# MCU.net
KiCad netlist of a schematic drawn in Altium Designer
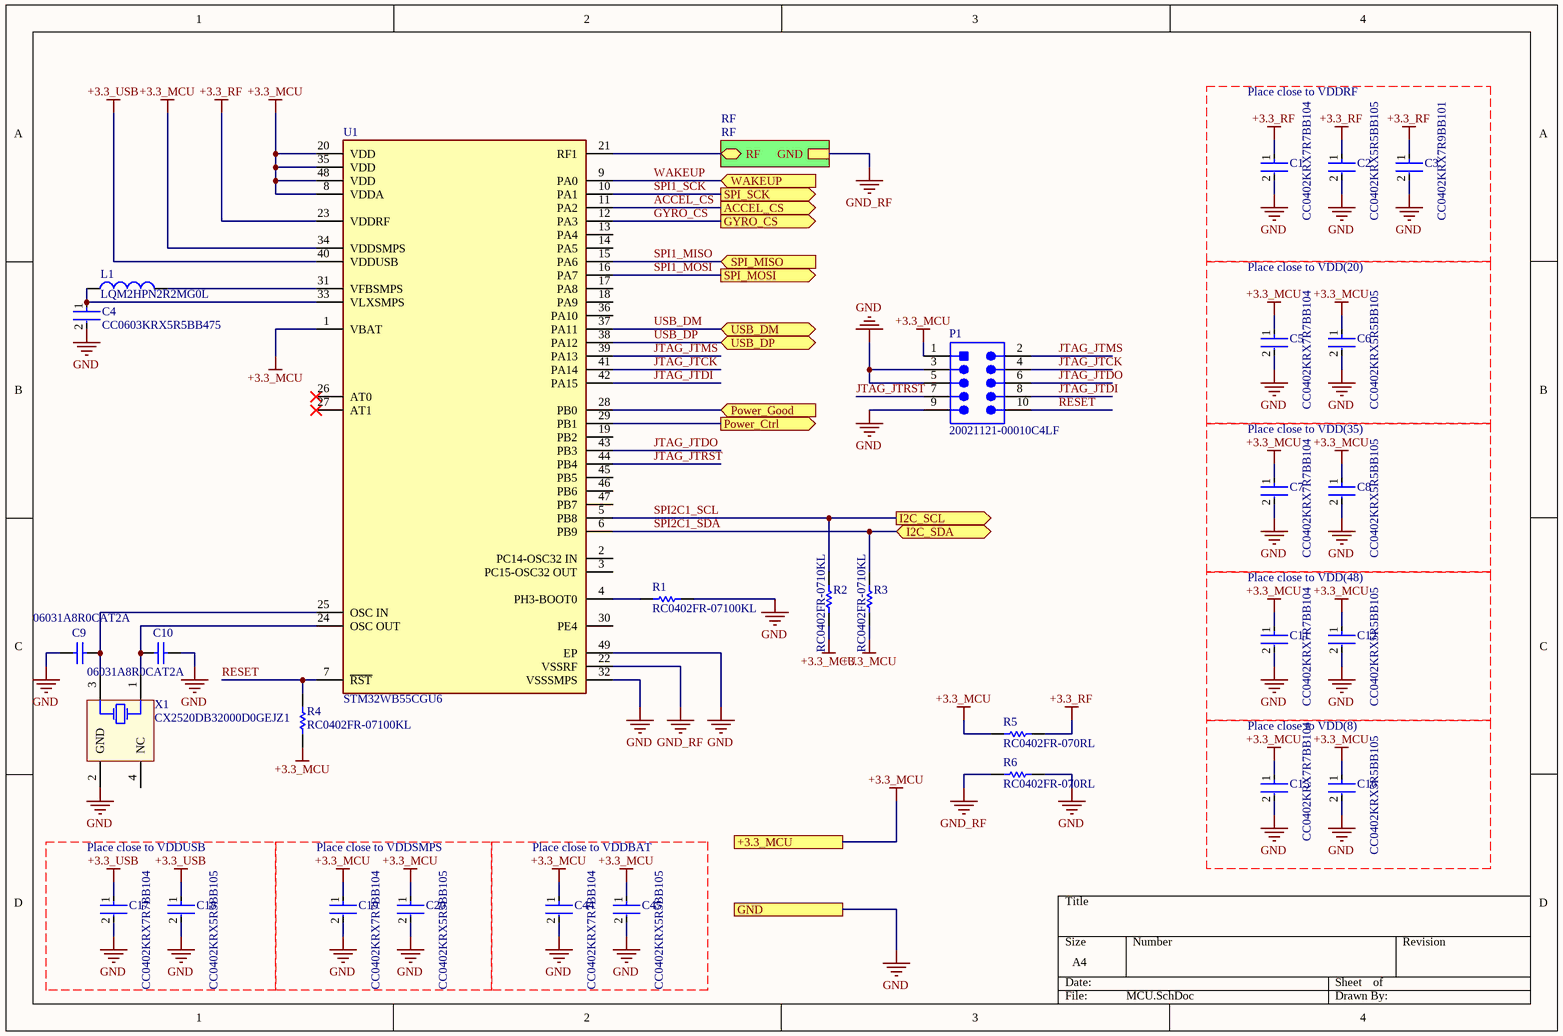
[diagram p0: MCU.SchDoc]

(export (version "E")
  (design (tool "Eeschema 10.0.6"))
  (components
    (comp (ref "C1")
      (value "CC0402KRX7R7BB104")
      (footprint "FP-CC0402-MFG")
      (description "CAP CER 0.1UF 16V X7R 0402")
      (fields (field (name "MANUFACTURER") "YAGEO") (field (name "TOLERANCE") "0.1"))
      (libsource (lib "Altium Content Vault") (part "11868f565c42a9108669ba33697ecf6"))
    )
    (comp (ref "C2")
      (value "CC0402KRX5R5BB105")
      (footprint "FP-CC0402-MFG")
      (description "CAP CER 1UF 6.3V X5R 0402")
      (fields
        (field (name "MANUFACTURER") "YAGEO")
        (field (name "OCTOPART") "https://octopart.com/cc0402krx5r5bb105-yageo-42244618")
      )
      (libsource (lib "Altium Content Vault") (part "11868f565c42a9108669ba33697ecf6"))
    )
    (comp (ref "C3")
      (value "CC0402KRX7R9BB101")
      (footprint "FP-CC0402-MFG")
      (description "CAP CER 100PF 50V X7R 0402")
      (fields
        (field (name "MANUFACTURER") "YAGEO")
        (field (name "OCTOPART") "https://octopart.com/cc0402krx7r9bb101-yageo-42334067")
      )
      (libsource (lib "Altium Content Vault") (part "11868f565c42a9108669ba33697ecf6"))
    )
    (comp (ref "C4")
      (value "CC0603KRX5R5BB475")
      (footprint "FP-CC0603-DA-MFG")
      (description "CAP CER 4.7UF 6.3V X5R 0603")
      (fields (field (name "TOLERANCE") "0.1") (field (name "VOLTAGE") "6.3 V"))
      (libsource (lib "Altium Content Vault") (part "11868f565c42a9108669ba33697ecf6"))
    )
    (comp (ref "C5")
      (value "CC0402KRX7R7BB104")
      (footprint "FP-CC0402-MFG")
      (description "CAP CER 0.1UF 16V X7R 0402")
      (fields (field (name "MANUFACTURER") "YAGEO") (field (name "TOLERANCE") "0.1"))
      (libsource (lib "Altium Content Vault") (part "11868f565c42a9108669ba33697ecf6"))
    )
    (comp (ref "C6")
      (value "CC0402KRX5R5BB105")
      (footprint "FP-CC0402-MFG")
      (description "CAP CER 1UF 6.3V X5R 0402")
      (fields
        (field (name "MANUFACTURER") "YAGEO")
        (field (name "OCTOPART") "https://octopart.com/cc0402krx5r5bb105-yageo-42244618")
      )
      (libsource (lib "Altium Content Vault") (part "11868f565c42a9108669ba33697ecf6"))
    )
    (comp (ref "C7")
      (value "CC0402KRX7R7BB104")
      (footprint "FP-CC0402-MFG")
      (description "CAP CER 0.1UF 16V X7R 0402")
      (fields (field (name "MANUFACTURER") "YAGEO") (field (name "TOLERANCE") "0.1"))
      (libsource (lib "Altium Content Vault") (part "11868f565c42a9108669ba33697ecf6"))
    )
    (comp (ref "C8")
      (value "CC0402KRX5R5BB105")
      (footprint "FP-CC0402-MFG")
      (description "CAP CER 1UF 6.3V X5R 0402")
      (fields
        (field (name "MANUFACTURER") "YAGEO")
        (field (name "OCTOPART") "https://octopart.com/cc0402krx5r5bb105-yageo-42244618")
      )
      (libsource (lib "Altium Content Vault") (part "11868f565c42a9108669ba33697ecf6"))
    )
    (comp (ref "C9")
      (value "06031A8R0CAT2A")
      (footprint "CAPC1608X90X35LL15T15")
      (fields (field (name "MANUFACTURER") "AVX Interconnect / Elco"))
      (libsource (lib "Altium Content Vault") (part "CAP"))
    )
    (comp (ref "C10")
      (value "06031A8R0CAT2A")
      (footprint "CAPC1608X90X35LL15T15")
      (fields (field (name "MANUFACTURER") "AVX Interconnect / Elco"))
      (libsource (lib "Altium Content Vault") (part "CAP"))
    )
    (comp (ref "C11")
      (value "CC0402KRX7R7BB104")
      (footprint "FP-CC0402-MFG")
      (description "CAP CER 0.1UF 16V X7R 0402")
      (fields (field (name "MANUFACTURER") "YAGEO") (field (name "TOLERANCE") "0.1"))
      (libsource (lib "Altium Content Vault") (part "11868f565c42a9108669ba33697ecf6"))
    )
    (comp (ref "C12")
      (value "CC0402KRX5R5BB105")
      (footprint "FP-CC0402-MFG")
      (description "CAP CER 1UF 6.3V X5R 0402")
      (fields
        (field (name "MANUFACTURER") "YAGEO")
        (field (name "OCTOPART") "https://octopart.com/cc0402krx5r5bb105-yageo-42244618")
      )
      (libsource (lib "Altium Content Vault") (part "11868f565c42a9108669ba33697ecf6"))
    )
    (comp (ref "C15")
      (value "CC0402KRX7R7BB104")
      (footprint "FP-CC0402-MFG")
      (description "CAP CER 0.1UF 16V X7R 0402")
      (fields (field (name "MANUFACTURER") "YAGEO") (field (name "TOLERANCE") "0.1"))
      (libsource (lib "Altium Content Vault") (part "11868f565c42a9108669ba33697ecf6"))
    )
    (comp (ref "C16")
      (value "CC0402KRX5R5BB105")
      (footprint "FP-CC0402-MFG")
      (description "CAP CER 1UF 6.3V X5R 0402")
      (fields
        (field (name "MANUFACTURER") "YAGEO")
        (field (name "OCTOPART") "https://octopart.com/cc0402krx5r5bb105-yageo-42244618")
      )
      (libsource (lib "Altium Content Vault") (part "11868f565c42a9108669ba33697ecf6"))
    )
    (comp (ref "C17")
      (value "CC0402KRX7R7BB104")
      (footprint "FP-CC0402-MFG")
      (description "CAP CER 0.1UF 16V X7R 0402")
      (fields (field (name "MANUFACTURER") "YAGEO") (field (name "TOLERANCE") "0.1"))
      (libsource (lib "Altium Content Vault") (part "11868f565c42a9108669ba33697ecf6"))
    )
    (comp (ref "C18")
      (value "CC0402KRX5R5BB105")
      (footprint "FP-CC0402-MFG")
      (description "CAP CER 1UF 6.3V X5R 0402")
      (fields
        (field (name "MANUFACTURER") "YAGEO")
        (field (name "OCTOPART") "https://octopart.com/cc0402krx5r5bb105-yageo-42244618")
      )
      (libsource (lib "Altium Content Vault") (part "11868f565c42a9108669ba33697ecf6"))
    )
    (comp (ref "C19")
      (value "CC0402KRX7R7BB104")
      (footprint "FP-CC0402-MFG")
      (description "CAP CER 0.1UF 16V X7R 0402")
      (fields (field (name "MANUFACTURER") "YAGEO") (field (name "TOLERANCE") "0.1"))
      (libsource (lib "Altium Content Vault") (part "11868f565c42a9108669ba33697ecf6"))
    )
    (comp (ref "C20")
      (value "CC0402KRX5R5BB105")
      (footprint "FP-CC0402-MFG")
      (description "CAP CER 1UF 6.3V X5R 0402")
      (fields
        (field (name "MANUFACTURER") "YAGEO")
        (field (name "OCTOPART") "https://octopart.com/cc0402krx5r5bb105-yageo-42244618")
      )
      (libsource (lib "Altium Content Vault") (part "11868f565c42a9108669ba33697ecf6"))
    )
    (comp (ref "C44")
      (value "CC0402KRX7R7BB104")
      (footprint "FP-CC0402-MFG")
      (description "CAP CER 0.1UF 16V X7R 0402")
      (fields (field (name "MANUFACTURER") "YAGEO") (field (name "TOLERANCE") "0.1"))
      (libsource (lib "Altium Content Vault") (part "11868f565c42a9108669ba33697ecf6"))
    )
    (comp (ref "C45")
      (value "CC0402KRX5R5BB105")
      (footprint "FP-CC0402-MFG")
      (description "CAP CER 1UF 6.3V X5R 0402")
      (fields
        (field (name "MANUFACTURER") "YAGEO")
        (field (name "OCTOPART") "https://octopart.com/cc0402krx5r5bb105-yageo-42244618")
      )
      (libsource (lib "Altium Content Vault") (part "11868f565c42a9108669ba33697ecf6"))
    )
    (comp (ref "L1")
      (value "LQM2HPN2R2MG0L")
      (footprint "INDC2520X100X60ML20T20")
      (description "Chip Inductor, 2.2 uH, +/- 20%, -55 to 125 degC, 1008 (2520 Metric), RoHS, Tape and Reel")
      (fields (field (name "TOLERANCE") "20%"))
      (libsource (lib "Altium Content Vault") (part "IND-2"))
    )
    (comp (ref "P1")
      (value "20021121-00010C4LF")
      (footprint "HDR2X5_SMT")
      (description "Male Header, Pitch 1.27 mm, 2 x 5 Position, Height 4.55 mm, -40 to 85 degC, RoHS, Tape and Reel")
      (fields (field (name "MANUFACTURER") "FCI"))
      (libsource (lib "Altium Content Vault") (part "CN-2P-M-R10"))
    )
    (comp (ref "R1")
      (value "RC0402FR-07100KL")
      (footprint "RESC1005X40X25NL05T10")
      (fields (field (name "MANUFACTURER") "Yageo / Phycomp"))
      (libsource (lib "Altium Content Vault") (part "RES"))
    )
    (comp (ref "R2")
      (value "RC0402FR-0710KL")
      (footprint "RESC1005X40X25ML05T10")
      (fields (field (name "MANUFACTURER") "Yageo / Phycomp"))
      (libsource (lib "Altium Content Vault") (part "RES"))
    )
    (comp (ref "R3")
      (value "RC0402FR-0710KL")
      (footprint "RESC1005X40X25ML05T10")
      (fields (field (name "MANUFACTURER") "Yageo / Phycomp"))
      (libsource (lib "Altium Content Vault") (part "RES"))
    )
    (comp (ref "R4")
      (value "RC0402FR-07100KL")
      (footprint "RESC1005X40X25NL05T10")
      (fields (field (name "MANUFACTURER") "Yageo / Phycomp"))
      (libsource (lib "Altium Content Vault") (part "RES"))
    )
    (comp (ref "R5")
      (value "RC0402FR-070RL")
      (footprint "RESC1005X40X25NL05T10")
      (fields (field (name "MANUFACTURER") "Yageo"))
      (libsource (lib "Altium Content Vault") (part "RES"))
    )
    (comp (ref "R6")
      (value "RC0402FR-070RL")
      (footprint "RESC1005X40X25NL05T10")
      (fields (field (name "MANUFACTURER") "Yageo"))
      (libsource (lib "Altium Content Vault") (part "RES"))
    )
    (comp (ref "U1")
      (value "STM32WB55CGU6")
      (footprint "FP-STM32WB55CGU6-MFG")
      (description "ULTRA-LOW-POWER DUAL CORE ARM CO")
      (fields
        (field (name "OCTOPART") "https://octopart.com/stm32wb55cgu6-stmicroelectronics-98750847")
        (field (name "MANUFACTURER") "STMicroelectronics")
      )
      (libsource (lib "Altium Content Vault") (part "9d9ca7f3567da95c474f3f549f05e68"))
    )
    (comp (ref "X1")
      (value "CX2520DB32000D0GEJZ1")
      (footprint "AVX-CX2520DB32000D0GEJZ1-4_V")
      (description "Crystal, 32 MHz, 8 pF, -10 to 70 degC, Surface Mount 2.5 x 2.0 mm")
      (fields (field (name "MANUFACTURER") "Kyocera"))
      (libsource (lib "Altium Content Vault") (part "AVX-CX2520DB32000D0GEJZ1-4"))
    )
  )
  (nets
    (net (code "1") (name "+3.3_MCU") (class "Default")
      (node (ref "C11") (pin "1") (pinfunction "1_1") (pintype "passive"))
      (node (ref "C12") (pin "1") (pinfunction "1_1") (pintype "passive"))
      (node (ref "C15") (pin "1") (pinfunction "1_1") (pintype "passive"))
      (node (ref "C16") (pin "1") (pinfunction "1_1") (pintype "passive"))
      (node (ref "C19") (pin "1") (pinfunction "1_1") (pintype "passive"))
      (node (ref "C20") (pin "1") (pinfunction "1_1") (pintype "passive"))
      (node (ref "C44") (pin "1") (pinfunction "1_1") (pintype "passive"))
      (node (ref "C45") (pin "1") (pinfunction "1_1") (pintype "passive"))
      (node (ref "C5") (pin "1") (pinfunction "1_1") (pintype "passive"))
      (node (ref "C6") (pin "1") (pinfunction "1_1") (pintype "passive"))
      (node (ref "C7") (pin "1") (pinfunction "1_1") (pintype "passive"))
      (node (ref "C8") (pin "1") (pinfunction "1_1") (pintype "passive"))
      (node (ref "P1") (pin "1") (pinfunction "1_1") (pintype "passive"))
      (node (ref "R2") (pin "1") (pinfunction "1_1") (pintype "passive"))
      (node (ref "R3") (pin "1") (pinfunction "1_1") (pintype "passive"))
      (node (ref "R4") (pin "1") (pinfunction "1_1") (pintype "passive"))
      (node (ref "R5") (pin "1") (pinfunction "1_1") (pintype "passive"))
      (node (ref "U1") (pin "1") (pinfunction "VBAT_1") (pintype "passive"))
      (node (ref "U1") (pin "20") (pinfunction "VDD_20") (pintype "passive"))
      (node (ref "U1") (pin "34") (pinfunction "VDDSMPS_34") (pintype "passive"))
      (node (ref "U1") (pin "35") (pinfunction "VDD_35") (pintype "passive"))
      (node (ref "U1") (pin "48") (pinfunction "VDD_48") (pintype "passive"))
      (node (ref "U1") (pin "8") (pinfunction "VDDA_8") (pintype "passive"))
    )
    (net (code "2") (name "+3.3_RF") (class "Default")
      (node (ref "C1") (pin "1") (pinfunction "1_1") (pintype "passive"))
      (node (ref "C2") (pin "1") (pinfunction "1_1") (pintype "passive"))
      (node (ref "C3") (pin "1") (pinfunction "1_1") (pintype "passive"))
      (node (ref "R5") (pin "2") (pinfunction "2_2") (pintype "passive"))
      (node (ref "U1") (pin "23") (pinfunction "VDDRF_23") (pintype "passive"))
    )
    (net (code "3") (name "+3.3_USB") (class "Default")
      (node (ref "C17") (pin "1") (pinfunction "1_1") (pintype "passive"))
      (node (ref "C18") (pin "1") (pinfunction "1_1") (pintype "passive"))
      (node (ref "U1") (pin "40") (pinfunction "VDDUSB_40") (pintype "passive"))
    )
    (net (code "4") (name "/ACCEL_CS") (class "Default")
      (node (ref "U1") (pin "11") (pinfunction "PA2_11") (pintype "passive"))
    )
    (net (code "5") (name "/GYRO_CS") (class "Default")
      (node (ref "U1") (pin "12") (pinfunction "PA3_12") (pintype "passive"))
    )
    (net (code "6") (name "/JTAG_JTCK") (class "Default")
      (node (ref "P1") (pin "4") (pinfunction "4_4") (pintype "passive"))
      (node (ref "U1") (pin "41") (pinfunction "PA14_41") (pintype "passive"))
    )
    (net (code "7") (name "/JTAG_JTDI") (class "Default")
      (node (ref "P1") (pin "8") (pinfunction "8_8") (pintype "passive"))
      (node (ref "U1") (pin "42") (pinfunction "PA15_42") (pintype "passive"))
    )
    (net (code "8") (name "/JTAG_JTDO") (class "Default")
      (node (ref "P1") (pin "6") (pinfunction "6_6") (pintype "passive"))
      (node (ref "U1") (pin "43") (pinfunction "PB3_43") (pintype "passive"))
    )
    (net (code "9") (name "/JTAG_JTMS") (class "Default")
      (node (ref "P1") (pin "2") (pinfunction "2_2") (pintype "passive"))
      (node (ref "U1") (pin "39") (pinfunction "PA13_39") (pintype "passive"))
    )
    (net (code "10") (name "/JTAG_JTRST") (class "Default")
      (node (ref "P1") (pin "7") (pinfunction "7_7") (pintype "passive"))
      (node (ref "U1") (pin "44") (pinfunction "PB4_44") (pintype "passive"))
    )
    (net (code "11") (name "/Power_Ctrl") (class "Default")
      (node (ref "U1") (pin "29") (pinfunction "PB1_29") (pintype "passive"))
    )
    (net (code "12") (name "/Power_Good") (class "Default")
      (node (ref "U1") (pin "28") (pinfunction "PB0_28") (pintype "passive"))
    )
    (net (code "13") (name "/RESET") (class "Default")
      (node (ref "P1") (pin "10") (pinfunction "10_10") (pintype "passive"))
      (node (ref "R4") (pin "2") (pinfunction "2_2") (pintype "passive"))
      (node (ref "U1") (pin "7") (pinfunction "~{RST}_7") (pintype "passive"))
    )
    (net (code "14") (name "/RF") (class "Default")
      (node (ref "U1") (pin "21") (pinfunction "RF1_21") (pintype "passive"))
    )
    (net (code "15") (name "/SPI1_MISO") (class "Default")
      (node (ref "U1") (pin "15") (pinfunction "PA6_15") (pintype "passive"))
    )
    (net (code "16") (name "/SPI1_MOSI") (class "Default")
      (node (ref "U1") (pin "16") (pinfunction "PA7_16") (pintype "passive"))
    )
    (net (code "17") (name "/SPI1_SCK") (class "Default")
      (node (ref "U1") (pin "10") (pinfunction "PA1_10") (pintype "passive"))
    )
    (net (code "18") (name "/SPI2C1_SCL") (class "Default")
      (node (ref "R2") (pin "2") (pinfunction "2_2") (pintype "passive"))
      (node (ref "U1") (pin "5") (pinfunction "PB8_5") (pintype "passive"))
    )
    (net (code "19") (name "/SPI2C1_SDA") (class "Default")
      (node (ref "R3") (pin "2") (pinfunction "2_2") (pintype "passive"))
      (node (ref "U1") (pin "6") (pinfunction "PB9_6") (pintype "passive"))
    )
    (net (code "20") (name "/USB_DM") (class "Default")
      (node (ref "U1") (pin "37") (pinfunction "PA11_37") (pintype "passive"))
    )
    (net (code "21") (name "/USB_DP") (class "Default")
      (node (ref "U1") (pin "38") (pinfunction "PA12_38") (pintype "passive"))
    )
    (net (code "22") (name "/WAKEUP") (class "Default")
      (node (ref "U1") (pin "9") (pinfunction "PA0_9") (pintype "passive"))
    )
    (net (code "23") (name "GND") (class "Default")
      (node (ref "C1") (pin "2") (pinfunction "2_2") (pintype "passive"))
      (node (ref "C10") (pin "2") (pinfunction "2_2") (pintype "passive"))
      (node (ref "C11") (pin "2") (pinfunction "2_2") (pintype "passive"))
      (node (ref "C12") (pin "2") (pinfunction "2_2") (pintype "passive"))
      (node (ref "C15") (pin "2") (pinfunction "2_2") (pintype "passive"))
      (node (ref "C16") (pin "2") (pinfunction "2_2") (pintype "passive"))
      (node (ref "C17") (pin "2") (pinfunction "2_2") (pintype "passive"))
      (node (ref "C18") (pin "2") (pinfunction "2_2") (pintype "passive"))
      (node (ref "C19") (pin "2") (pinfunction "2_2") (pintype "passive"))
      (node (ref "C2") (pin "2") (pinfunction "2_2") (pintype "passive"))
      (node (ref "C20") (pin "2") (pinfunction "2_2") (pintype "passive"))
      (node (ref "C3") (pin "2") (pinfunction "2_2") (pintype "passive"))
      (node (ref "C4") (pin "2") (pinfunction "2_2") (pintype "passive"))
      (node (ref "C44") (pin "2") (pinfunction "2_2") (pintype "passive"))
      (node (ref "C45") (pin "2") (pinfunction "2_2") (pintype "passive"))
      (node (ref "C5") (pin "2") (pinfunction "2_2") (pintype "passive"))
      (node (ref "C6") (pin "2") (pinfunction "2_2") (pintype "passive"))
      (node (ref "C7") (pin "2") (pinfunction "2_2") (pintype "passive"))
      (node (ref "C8") (pin "2") (pinfunction "2_2") (pintype "passive"))
      (node (ref "C9") (pin "1") (pinfunction "1_1") (pintype "passive"))
      (node (ref "P1") (pin "3") (pinfunction "3_3") (pintype "passive"))
      (node (ref "P1") (pin "5") (pinfunction "5_5") (pintype "passive"))
      (node (ref "P1") (pin "9") (pinfunction "9_9") (pintype "passive"))
      (node (ref "R1") (pin "1") (pinfunction "1_1") (pintype "passive"))
      (node (ref "R6") (pin "2") (pinfunction "2_2") (pintype "passive"))
      (node (ref "U1") (pin "32") (pinfunction "VSSSMPS_32") (pintype "passive"))
      (node (ref "U1") (pin "49") (pinfunction "EP_49") (pintype "power_in"))
      (node (ref "X1") (pin "2") (pinfunction "GND_2") (pintype "power_in"))
    )
    (net (code "24") (name "GND_RF") (class "Default")
      (node (ref "R6") (pin "1") (pinfunction "1_1") (pintype "passive"))
      (node (ref "U1") (pin "22") (pinfunction "VSSRF_22") (pintype "passive"))
    )
    (net (code "25") (name "Net-(U1-OSC_IN)") (class "Default")
      (node (ref "C9") (pin "2") (pinfunction "2_2") (pintype "passive"))
      (node (ref "U1") (pin "25") (pinfunction "OSC_IN_25") (pintype "passive"))
      (node (ref "X1") (pin "3") (pinfunction "HOT_3") (pintype "passive"))
    )
    (net (code "26") (name "Net-(U1-OSC_OUT)") (class "Default")
      (node (ref "C10") (pin "1") (pinfunction "1_1") (pintype "passive"))
      (node (ref "U1") (pin "24") (pinfunction "OSC_OUT_24") (pintype "passive"))
      (node (ref "X1") (pin "1") (pinfunction "HOT_1") (pintype "passive"))
    )
    (net (code "27") (name "Net-(U1-PH3-BOOT0)") (class "Default")
      (node (ref "R1") (pin "2") (pinfunction "2_2") (pintype "passive"))
      (node (ref "U1") (pin "4") (pinfunction "PH3-BOOT0_4") (pintype "passive"))
    )
    (net (code "28") (name "Net-(U1-VFBSMPS)") (class "Default")
      (node (ref "L1") (pin "2") (pinfunction "2_2") (pintype "passive"))
      (node (ref "U1") (pin "31") (pinfunction "VFBSMPS_31") (pintype "passive"))
    )
    (net (code "29") (name "Net-(U1-VLXSMPS)") (class "Default")
      (node (ref "C4") (pin "1") (pinfunction "1_1") (pintype "passive"))
      (node (ref "L1") (pin "1") (pinfunction "1_1") (pintype "passive"))
      (node (ref "U1") (pin "33") (pinfunction "VLXSMPS_33") (pintype "passive"))
    )
    (net (code "30") (name "unconnected-(U1-AT0-Pad26)") (class "Default")
      (node (ref "U1") (pin "26") (pinfunction "AT0_26") (pintype "passive+no_connect"))
    )
    (net (code "31") (name "unconnected-(U1-AT1-Pad27)") (class "Default")
      (node (ref "U1") (pin "27") (pinfunction "AT1_27") (pintype "passive+no_connect"))
    )
    (net (code "32") (name "unconnected-(U1-PA4-Pad13)") (class "Default")
      (node (ref "U1") (pin "13") (pinfunction "PA4_13") (pintype "passive"))
    )
    (net (code "33") (name "unconnected-(U1-PA5-Pad14)") (class "Default")
      (node (ref "U1") (pin "14") (pinfunction "PA5_14") (pintype "passive"))
    )
    (net (code "34") (name "unconnected-(U1-PA8-Pad17)") (class "Default")
      (node (ref "U1") (pin "17") (pinfunction "PA8_17") (pintype "passive"))
    )
    (net (code "35") (name "unconnected-(U1-PA9-Pad18)") (class "Default")
      (node (ref "U1") (pin "18") (pinfunction "PA9_18") (pintype "passive"))
    )
    (net (code "36") (name "unconnected-(U1-PA10-Pad36)") (class "Default")
      (node (ref "U1") (pin "36") (pinfunction "PA10_36") (pintype "passive"))
    )
    (net (code "37") (name "unconnected-(U1-PB2-Pad19)") (class "Default")
      (node (ref "U1") (pin "19") (pinfunction "PB2_19") (pintype "passive"))
    )
    (net (code "38") (name "unconnected-(U1-PB5-Pad45)") (class "Default")
      (node (ref "U1") (pin "45") (pinfunction "PB5_45") (pintype "passive"))
    )
    (net (code "39") (name "unconnected-(U1-PB6-Pad46)") (class "Default")
      (node (ref "U1") (pin "46") (pinfunction "PB6_46") (pintype "passive"))
    )
    (net (code "40") (name "unconnected-(U1-PB7-Pad47)") (class "Default")
      (node (ref "U1") (pin "47") (pinfunction "PB7_47") (pintype "passive"))
    )
    (net (code "41") (name "unconnected-(U1-PC14-OSC32_IN-Pad2)") (class "Default")
      (node (ref "U1") (pin "2") (pinfunction "PC14-OSC32_IN_2") (pintype "passive"))
    )
    (net (code "42") (name "unconnected-(U1-PC15-OSC32_OUT-Pad3)") (class "Default")
      (node (ref "U1") (pin "3") (pinfunction "PC15-OSC32_OUT_3") (pintype "passive"))
    )
    (net (code "43") (name "unconnected-(U1-PE4-Pad30)") (class "Default")
      (node (ref "U1") (pin "30") (pinfunction "PE4_30") (pintype "passive"))
    )
    (net (code "44") (name "unconnected-(X1-NC-Pad4)") (class "Default")
      (node (ref "X1") (pin "4") (pinfunction "NC_4") (pintype "passive"))
    )
  )
)
